# Power_PMIC.net
KiCad netlist of a schematic drawn in Altium Designer
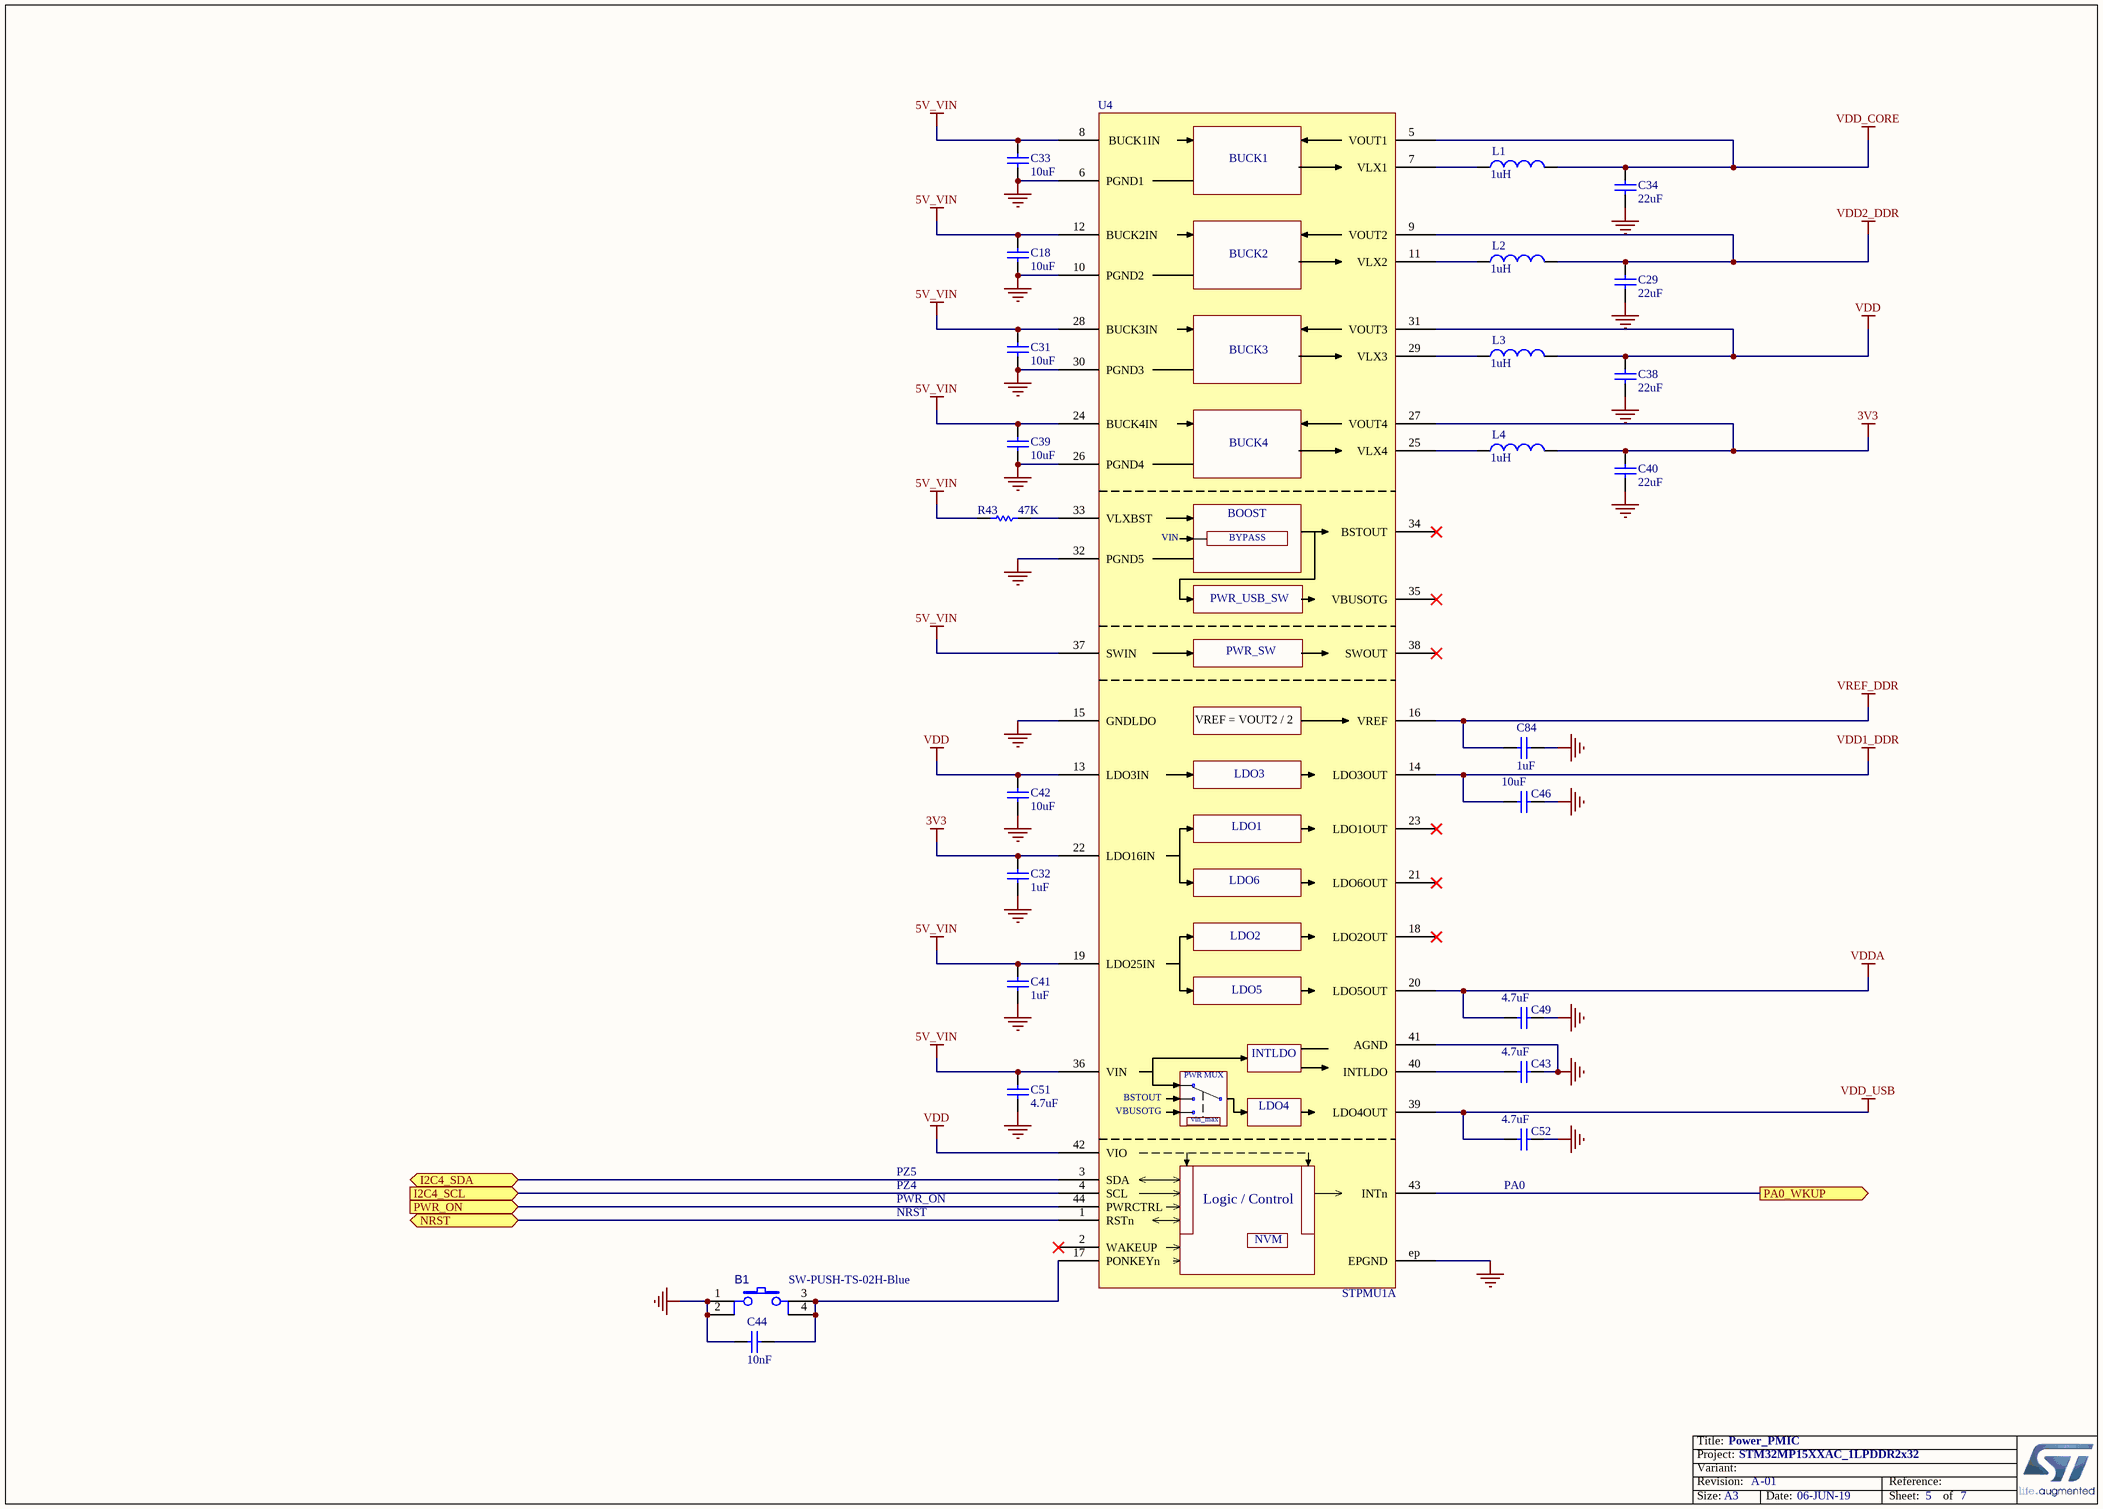
[diagram p0: Power_PMIC.SchDoc]

(export (version "E")
  (design (tool "Eeschema 10.0.6"))
  (components
    (comp (ref "B1")
      (value "SW-PUSH-TS-02H-Blue")
      (footprint "SWI_JIUBABA_C-TS-02H-2-5-B-V-T_R_BLUE")
      (description "Switch HW SMD blue")
      (fields
        (field (name "INTERNAL_PART_NUMBER") "MCD-00172")
        (field (name "MANUFACTURER_PART_NUMBER") "C-TS-02H-2.5-B-V-T/R BLUE")
        (field (name "PROVIDED_BY") "SUBCO")
      )
      (libsource (lib "MCD_PARTS_database") (part "SW-PUSH-TS-02H-Blue"))
    )
    (comp (ref "C18")
      (value "10uF")
      (footprint "C0603")
      (description "Capacitor, MLCC, 10uF, 10V, X5R, 10%, 0603, T=0,8mm")
      (fields
        (field (name "INTERNAL_PART_NUMBER") "MCD-00099")
        (field (name "MANUFACTURER_PART_NUMBER") "GRM188R61A106KE69D")
        (field (name "PROVIDED_BY") "SUBCO")
      )
      (libsource (lib "MCD_PARTS_database") (part "Capacitor"))
    )
    (comp (ref "C29")
      (value "22uF")
      (footprint "C0603")
      (description "Capacitor, MLCC, 22uF, 6V3, X5R, 20%, 0603, T=0,8mm")
      (fields
        (field (name "INTERNAL_PART_NUMBER") "MCD-00100")
        (field (name "MANUFACTURER_PART_NUMBER") "GRM188R60J226MEA0J")
        (field (name "PROVIDED_BY") "SUBCO")
      )
      (libsource (lib "MCD_PARTS_database") (part "Capacitor"))
    )
    (comp (ref "C31")
      (value "10uF")
      (footprint "C0603")
      (description "Capacitor, MLCC, 10uF, 10V, X5R, 10%, 0603, T=0,8mm")
      (fields
        (field (name "INTERNAL_PART_NUMBER") "MCD-00099")
        (field (name "MANUFACTURER_PART_NUMBER") "GRM188R61A106KE69D")
        (field (name "PROVIDED_BY") "SUBCO")
      )
      (libsource (lib "MCD_PARTS_database") (part "Capacitor"))
    )
    (comp (ref "C32")
      (value "1uF")
      (footprint "C0402")
      (description "Capacitor, MLCC, 1uF, 25V, X5R, 10%, 0402, T=0,5mm")
      (fields
        (field (name "INTERNAL_PART_NUMBER") "MCD-00095")
        (field (name "MANUFACTURER_PART_NUMBER") "GRM155R61E105KA12")
        (field (name "PROVIDED_BY") "SUBCO")
      )
      (libsource (lib "MCD_PARTS_database") (part "Capacitor"))
    )
    (comp (ref "C33")
      (value "10uF")
      (footprint "C0603")
      (description "Capacitor, MLCC, 10uF, 10V, X5R, 10%, 0603, T=0,8mm")
      (fields
        (field (name "INTERNAL_PART_NUMBER") "MCD-00099")
        (field (name "MANUFACTURER_PART_NUMBER") "GRM188R61A106KE69D")
        (field (name "PROVIDED_BY") "SUBCO")
      )
      (libsource (lib "MCD_PARTS_database") (part "Capacitor"))
    )
    (comp (ref "C34")
      (value "22uF")
      (footprint "C0603")
      (description "Capacitor, MLCC, 22uF, 6V3, X5R, 20%, 0603, T=0,8mm")
      (fields
        (field (name "INTERNAL_PART_NUMBER") "MCD-00100")
        (field (name "MANUFACTURER_PART_NUMBER") "GRM188R60J226MEA0J")
        (field (name "PROVIDED_BY") "SUBCO")
      )
      (libsource (lib "MCD_PARTS_database") (part "Capacitor"))
    )
    (comp (ref "C38")
      (value "22uF")
      (footprint "C0603")
      (description "Capacitor, MLCC, 22uF, 6V3, X5R, 20%, 0603, T=0,8mm")
      (fields
        (field (name "INTERNAL_PART_NUMBER") "MCD-00100")
        (field (name "MANUFACTURER_PART_NUMBER") "GRM188R60J226MEA0J")
        (field (name "PROVIDED_BY") "SUBCO")
      )
      (libsource (lib "MCD_PARTS_database") (part "Capacitor"))
    )
    (comp (ref "C39")
      (value "10uF")
      (footprint "C0603")
      (description "Capacitor, MLCC, 10uF, 10V, X5R, 10%, 0603, T=0,8mm")
      (fields
        (field (name "INTERNAL_PART_NUMBER") "MCD-00099")
        (field (name "MANUFACTURER_PART_NUMBER") "GRM188R61A106KE69D")
        (field (name "PROVIDED_BY") "SUBCO")
      )
      (libsource (lib "MCD_PARTS_database") (part "Capacitor"))
    )
    (comp (ref "C40")
      (value "22uF")
      (footprint "C0603")
      (description "Capacitor, MLCC, 22uF, 6V3, X5R, 20%, 0603, T=0,8mm")
      (fields
        (field (name "INTERNAL_PART_NUMBER") "MCD-00100")
        (field (name "MANUFACTURER_PART_NUMBER") "GRM188R60J226MEA0J")
        (field (name "PROVIDED_BY") "SUBCO")
      )
      (libsource (lib "MCD_PARTS_database") (part "Capacitor"))
    )
    (comp (ref "C41")
      (value "1uF")
      (footprint "C0402")
      (description "Capacitor, MLCC, 1uF, 25V, X5R, 10%, 0402, T=0,5mm")
      (fields
        (field (name "INTERNAL_PART_NUMBER") "MCD-00095")
        (field (name "MANUFACTURER_PART_NUMBER") "GRM155R61E105KA12")
        (field (name "PROVIDED_BY") "SUBCO")
      )
      (libsource (lib "MCD_PARTS_database") (part "Capacitor"))
    )
    (comp (ref "C42")
      (value "10uF")
      (footprint "C0603")
      (description "Capacitor, MLCC, 10uF, 10V, X5R, 10%, 0603, T=0,8mm")
      (fields
        (field (name "INTERNAL_PART_NUMBER") "MCD-00099")
        (field (name "MANUFACTURER_PART_NUMBER") "GRM188R61A106KE69D")
        (field (name "PROVIDED_BY") "SUBCO")
      )
      (libsource (lib "MCD_PARTS_database") (part "Capacitor"))
    )
    (comp (ref "C43")
      (value "4.7uF")
      (footprint "C0402")
      (description "Capacitor, MLCC, 4.7uF, 6V3, X5R, 20%, 0402, T=0,5mm")
      (fields
        (field (name "INTERNAL_PART_NUMBER") "MCD-00096")
        (field (name "MANUFACTURER_PART_NUMBER") "GRM155R60J475ME87")
        (field (name "PROVIDED_BY") "SUBCO")
      )
      (libsource (lib "MCD_PARTS_database") (part "Capacitor"))
    )
    (comp (ref "C44")
      (value "10nF")
      (footprint "C0402")
      (description "Capacitor, MLCC, 10nF, 16V, X7R, 10%, 0402, T=0.5mm")
      (fields
        (field (name "INTERNAL_PART_NUMBER") "MCD-00011")
        (field (name "MANUFACTURER_PART_NUMBER") "CC0402KRX7R7BB103")
        (field (name "PROVIDED_BY") "SUBCO")
      )
      (libsource (lib "MCD_PARTS_database") (part "Capacitor"))
    )
    (comp (ref "C46")
      (value "10uF")
      (footprint "C0603")
      (description "Capacitor, MLCC, 10uF, 10V, X5R, 10%, 0603, T=0,8mm")
      (fields
        (field (name "INTERNAL_PART_NUMBER") "MCD-00099")
        (field (name "MANUFACTURER_PART_NUMBER") "GRM188R61A106KE69D")
        (field (name "PROVIDED_BY") "SUBCO")
      )
      (libsource (lib "MCD_PARTS_database") (part "Capacitor"))
    )
    (comp (ref "C49")
      (value "4.7uF")
      (footprint "C0402")
      (description "Capacitor, MLCC, 4.7uF, 6V3, X5R, 20%, 0402, T=0,5mm")
      (fields
        (field (name "INTERNAL_PART_NUMBER") "MCD-00096")
        (field (name "MANUFACTURER_PART_NUMBER") "GRM155R60J475ME87")
        (field (name "PROVIDED_BY") "SUBCO")
      )
      (libsource (lib "MCD_PARTS_database") (part "Capacitor"))
    )
    (comp (ref "C51")
      (value "4.7uF")
      (footprint "C0402")
      (description "Capacitor, MLCC, 4.7uF, 6V3, X5R, 20%, 0402, T=0,5mm")
      (fields
        (field (name "INTERNAL_PART_NUMBER") "MCD-00096")
        (field (name "MANUFACTURER_PART_NUMBER") "GRM155R60J475ME87")
        (field (name "PROVIDED_BY") "SUBCO")
      )
      (libsource (lib "MCD_PARTS_database") (part "Capacitor"))
    )
    (comp (ref "C52")
      (value "4.7uF")
      (footprint "C0402")
      (description "Capacitor, MLCC, 4.7uF, 6V3, X5R, 20%, 0402, T=0,5mm")
      (fields
        (field (name "INTERNAL_PART_NUMBER") "MCD-00096")
        (field (name "MANUFACTURER_PART_NUMBER") "GRM155R60J475ME87")
        (field (name "PROVIDED_BY") "SUBCO")
      )
      (libsource (lib "MCD_PARTS_database") (part "Capacitor"))
    )
    (comp (ref "C84")
      (value "1uF")
      (footprint "C0402")
      (description "Capacitor, MLCC, 1uF, 25V, X5R, 10%, 0402, T=0,5mm")
      (fields
        (field (name "INTERNAL_PART_NUMBER") "MCD-00095")
        (field (name "MANUFACTURER_PART_NUMBER") "GRM155R61E105KA12")
        (field (name "PROVIDED_BY") "SUBCO")
      )
      (libsource (lib "MCD_PARTS_database") (part "Capacitor"))
    )
    (comp (ref "L1")
      (value "1uH")
      (footprint "IND_2520_TOKO_DFE252012P")
      (description "Power Inductor ,1uH,4.3A max,+/-20%,0.042ohm,2520")
      (fields
        (field (name "INTERNAL_PART_NUMBER") "MCD-01122")
        (field (name "MANUFACTURER_PART_NUMBER") "DFE252012P-1ROM=P2")
        (field (name "PROVIDED_BY") "SUBCO")
      )
      (libsource (lib "MCD_PARTS_database") (part "IND_1uH_42mohm_3.2A"))
    )
    (comp (ref "L2")
      (value "1uH")
      (footprint "IND_2520_TOKO_DFE252012P")
      (description "Power Inductor ,1uH,4.3A max,+/-20%,0.042ohm,2520")
      (fields
        (field (name "INTERNAL_PART_NUMBER") "MCD-01122")
        (field (name "MANUFACTURER_PART_NUMBER") "DFE252012P-1ROM=P2")
        (field (name "PROVIDED_BY") "SUBCO")
      )
      (libsource (lib "MCD_PARTS_database") (part "IND_1uH_42mohm_3.2A"))
    )
    (comp (ref "L3")
      (value "1uH")
      (footprint "IND_2520_TOKO_DFE252012P")
      (description "Power Inductor ,1uH,4.3A max,+/-20%,0.042ohm,2520")
      (fields
        (field (name "INTERNAL_PART_NUMBER") "MCD-01122")
        (field (name "MANUFACTURER_PART_NUMBER") "DFE252012P-1ROM=P2")
        (field (name "PROVIDED_BY") "SUBCO")
      )
      (libsource (lib "MCD_PARTS_database") (part "IND_1uH_42mohm_3.2A"))
    )
    (comp (ref "L4")
      (value "1uH")
      (footprint "IND_2520_TOKO_DFE252012P")
      (description "Power Inductor ,1uH,4.3A max,+/-20%,0.042ohm,2520")
      (fields
        (field (name "INTERNAL_PART_NUMBER") "MCD-01122")
        (field (name "MANUFACTURER_PART_NUMBER") "DFE252012P-1ROM=P2")
        (field (name "PROVIDED_BY") "SUBCO")
      )
      (libsource (lib "MCD_PARTS_database") (part "IND_1uH_42mohm_3.2A"))
    )
    (comp (ref "R43")
      (value "47K")
      (footprint "R0402")
      (description "Resistor,47K,0402,1%,1/16W")
      (fields
        (field (name "INTERNAL_PART_NUMBER") "MCD-00063")
        (field (name "MANUFACTURER_PART_NUMBER") "RC0402FR-0747KL")
        (field (name "PROVIDED_BY") "SUBCO")
      )
      (libsource (lib "MCD_PARTS_database") (part "Resistor"))
    )
    (comp (ref "U4")
      (value "STPMU1A")
      (footprint "ICC_WFQFN44-EPAD_5X6_P040")
      (description "STM PMIC WFQFN 5.0x6.0x0.80 44L 0.4 pitch")
      (fields
        (field (name "INTERNAL_PART_NUMBER") "MCD-00303")
        (field (name "MANUFACTURER_PART_NUMBER") "STPMU1APQR")
        (field (name "PROVIDED_BY") "SUBCO with ST control")
      )
      (libsource (lib "MCD_PARTS_database") (part "STPMU1"))
    )
  )
  (nets
    (net (code "1") (name "/I2C4_SCL") (class "Default")
      (node (ref "U4") (pin "4") (pinfunction "SCL_4") (pintype "passive"))
    )
    (net (code "2") (name "/I2C4_SDA") (class "Default")
      (node (ref "U4") (pin "3") (pinfunction "SDA_3") (pintype "passive"))
    )
    (net (code "3") (name "/NRST") (class "Default")
      (node (ref "U4") (pin "1") (pinfunction "RSTn_1") (pintype "passive"))
    )
    (net (code "4") (name "/PA0_WKUP") (class "Default")
      (node (ref "U4") (pin "43") (pinfunction "INTn_43") (pintype "passive"))
    )
    (net (code "5") (name "/PWR_ON") (class "Default")
      (node (ref "U4") (pin "44") (pinfunction "PWRCTRL_44") (pintype "passive"))
    )
    (net (code "6") (name "3V3") (class "Default")
      (node (ref "C32") (pin "2") (pinfunction "2_2") (pintype "passive"))
      (node (ref "C40") (pin "2") (pinfunction "2_2") (pintype "passive"))
      (node (ref "L4") (pin "2") (pinfunction "2_2") (pintype "passive"))
      (node (ref "U4") (pin "22") (pinfunction "LDO16IN_22") (pintype "passive"))
      (node (ref "U4") (pin "27") (pinfunction "VOUT4_27") (pintype "passive"))
    )
    (net (code "7") (name "5V_VIN") (class "Default")
      (node (ref "C18") (pin "2") (pinfunction "2_2") (pintype "passive"))
      (node (ref "C31") (pin "2") (pinfunction "2_2") (pintype "passive"))
      (node (ref "C33") (pin "2") (pinfunction "2_2") (pintype "passive"))
      (node (ref "C39") (pin "2") (pinfunction "2_2") (pintype "passive"))
      (node (ref "C41") (pin "2") (pinfunction "2_2") (pintype "passive"))
      (node (ref "C51") (pin "2") (pinfunction "2_2") (pintype "passive"))
      (node (ref "R43") (pin "2") (pinfunction "2_2") (pintype "passive"))
      (node (ref "U4") (pin "12") (pinfunction "BUCK2IN_12") (pintype "passive"))
      (node (ref "U4") (pin "19") (pinfunction "LDO25IN_19") (pintype "passive"))
      (node (ref "U4") (pin "24") (pinfunction "BUCK4IN_24") (pintype "passive"))
      (node (ref "U4") (pin "28") (pinfunction "BUCK3IN_28") (pintype "passive"))
      (node (ref "U4") (pin "36") (pinfunction "VIN_36") (pintype "passive"))
      (node (ref "U4") (pin "37") (pinfunction "SWIN_37") (pintype "passive"))
      (node (ref "U4") (pin "8") (pinfunction "BUCK1IN_8") (pintype "passive"))
    )
    (net (code "8") (name "GND") (class "Default")
      (node (ref "B1") (pin "1") (pinfunction "1_1") (pintype "passive"))
      (node (ref "B1") (pin "2") (pinfunction "2_2") (pintype "passive"))
      (node (ref "C18") (pin "1") (pinfunction "1_1") (pintype "passive"))
      (node (ref "C29") (pin "1") (pinfunction "1_1") (pintype "passive"))
      (node (ref "C31") (pin "1") (pinfunction "1_1") (pintype "passive"))
      (node (ref "C32") (pin "1") (pinfunction "1_1") (pintype "passive"))
      (node (ref "C33") (pin "1") (pinfunction "1_1") (pintype "passive"))
      (node (ref "C34") (pin "1") (pinfunction "1_1") (pintype "passive"))
      (node (ref "C38") (pin "1") (pinfunction "1_1") (pintype "passive"))
      (node (ref "C39") (pin "1") (pinfunction "1_1") (pintype "passive"))
      (node (ref "C40") (pin "1") (pinfunction "1_1") (pintype "passive"))
      (node (ref "C41") (pin "1") (pinfunction "1_1") (pintype "passive"))
      (node (ref "C42") (pin "1") (pinfunction "1_1") (pintype "passive"))
      (node (ref "C43") (pin "2") (pinfunction "2_2") (pintype "passive"))
      (node (ref "C44") (pin "1") (pinfunction "1_1") (pintype "passive"))
      (node (ref "C46") (pin "1") (pinfunction "1_1") (pintype "passive"))
      (node (ref "C49") (pin "1") (pinfunction "1_1") (pintype "passive"))
      (node (ref "C51") (pin "1") (pinfunction "1_1") (pintype "passive"))
      (node (ref "C52") (pin "1") (pinfunction "1_1") (pintype "passive"))
      (node (ref "C84") (pin "1") (pinfunction "1_1") (pintype "passive"))
      (node (ref "U4") (pin "10") (pinfunction "PGND2_10") (pintype "passive"))
      (node (ref "U4") (pin "15") (pinfunction "GNDLDO_15") (pintype "passive"))
      (node (ref "U4") (pin "26") (pinfunction "PGND4_26") (pintype "passive"))
      (node (ref "U4") (pin "30") (pinfunction "PGND3_30") (pintype "passive"))
      (node (ref "U4") (pin "32") (pinfunction "PGND5_32") (pintype "passive"))
      (node (ref "U4") (pin "41") (pinfunction "AGND_41") (pintype "passive"))
      (node (ref "U4") (pin "6") (pinfunction "PGND1_6") (pintype "passive"))
      (node (ref "U4") (pin "ep") (pinfunction "EPGND_ep") (pintype "passive"))
    )
    (net (code "9") (name "Net-(U4-INTLDO)") (class "Default")
      (node (ref "C43") (pin "1") (pinfunction "1_1") (pintype "passive"))
      (node (ref "U4") (pin "40") (pinfunction "INTLDO_40") (pintype "passive"))
    )
    (net (code "10") (name "Net-(U4-PONKEYn)") (class "Default")
      (node (ref "B1") (pin "3") (pinfunction "3_3") (pintype "passive"))
      (node (ref "B1") (pin "4") (pinfunction "4_4") (pintype "passive"))
      (node (ref "C44") (pin "2") (pinfunction "2_2") (pintype "passive"))
      (node (ref "U4") (pin "17") (pinfunction "PONKEYn_17") (pintype "passive"))
    )
    (net (code "11") (name "Net-(U4-VLX1)") (class "Default")
      (node (ref "L1") (pin "1") (pinfunction "1_1") (pintype "passive"))
      (node (ref "U4") (pin "7") (pinfunction "VLX1_7") (pintype "passive"))
    )
    (net (code "12") (name "Net-(U4-VLX2)") (class "Default")
      (node (ref "L2") (pin "1") (pinfunction "1_1") (pintype "passive"))
      (node (ref "U4") (pin "11") (pinfunction "VLX2_11") (pintype "passive"))
    )
    (net (code "13") (name "Net-(U4-VLX3)") (class "Default")
      (node (ref "L3") (pin "1") (pinfunction "1_1") (pintype "passive"))
      (node (ref "U4") (pin "29") (pinfunction "VLX3_29") (pintype "passive"))
    )
    (net (code "14") (name "Net-(U4-VLX4)") (class "Default")
      (node (ref "L4") (pin "1") (pinfunction "1_1") (pintype "passive"))
      (node (ref "U4") (pin "25") (pinfunction "VLX4_25") (pintype "passive"))
    )
    (net (code "15") (name "Net-(U4-VLXBST)") (class "Default")
      (node (ref "R43") (pin "1") (pinfunction "1_1") (pintype "passive"))
      (node (ref "U4") (pin "33") (pinfunction "VLXBST_33") (pintype "passive"))
    )
    (net (code "16") (name "VDD") (class "Default")
      (node (ref "C38") (pin "2") (pinfunction "2_2") (pintype "passive"))
      (node (ref "C42") (pin "2") (pinfunction "2_2") (pintype "passive"))
      (node (ref "L3") (pin "2") (pinfunction "2_2") (pintype "passive"))
      (node (ref "U4") (pin "13") (pinfunction "LDO3IN_13") (pintype "passive"))
      (node (ref "U4") (pin "31") (pinfunction "VOUT3_31") (pintype "passive"))
      (node (ref "U4") (pin "42") (pinfunction "VIO_42") (pintype "passive"))
    )
    (net (code "17") (name "VDD1_DDR") (class "Default")
      (node (ref "C46") (pin "2") (pinfunction "2_2") (pintype "passive"))
      (node (ref "U4") (pin "14") (pinfunction "LDO3OUT_14") (pintype "passive"))
    )
    (net (code "18") (name "VDD2_DDR") (class "Default")
      (node (ref "C29") (pin "2") (pinfunction "2_2") (pintype "passive"))
      (node (ref "L2") (pin "2") (pinfunction "2_2") (pintype "passive"))
      (node (ref "U4") (pin "9") (pinfunction "VOUT2_9") (pintype "passive"))
    )
    (net (code "19") (name "VDDA") (class "Default")
      (node (ref "C49") (pin "2") (pinfunction "2_2") (pintype "passive"))
      (node (ref "U4") (pin "20") (pinfunction "LDO5OUT_20") (pintype "passive"))
    )
    (net (code "20") (name "VDD_CORE") (class "Default")
      (node (ref "C34") (pin "2") (pinfunction "2_2") (pintype "passive"))
      (node (ref "L1") (pin "2") (pinfunction "2_2") (pintype "passive"))
      (node (ref "U4") (pin "5") (pinfunction "VOUT1_5") (pintype "passive"))
    )
    (net (code "21") (name "VDD_USB") (class "Default")
      (node (ref "C52") (pin "2") (pinfunction "2_2") (pintype "passive"))
      (node (ref "U4") (pin "39") (pinfunction "LDO4OUT_39") (pintype "passive"))
    )
    (net (code "22") (name "VREF_DDR") (class "Default")
      (node (ref "C84") (pin "2") (pinfunction "2_2") (pintype "passive"))
      (node (ref "U4") (pin "16") (pinfunction "VREF_16") (pintype "passive"))
    )
    (net (code "23") (name "unconnected-(U4-BSTOUT-Pad34)") (class "Default")
      (node (ref "U4") (pin "34") (pinfunction "BSTOUT_34") (pintype "passive+no_connect"))
    )
    (net (code "24") (name "unconnected-(U4-LDO1OUT-Pad23)") (class "Default")
      (node (ref "U4") (pin "23") (pinfunction "LDO1OUT_23") (pintype "passive+no_connect"))
    )
    (net (code "25") (name "unconnected-(U4-LDO2OUT-Pad18)") (class "Default")
      (node (ref "U4") (pin "18") (pinfunction "LDO2OUT_18") (pintype "passive+no_connect"))
    )
    (net (code "26") (name "unconnected-(U4-LDO6OUT-Pad21)") (class "Default")
      (node (ref "U4") (pin "21") (pinfunction "LDO6OUT_21") (pintype "passive+no_connect"))
    )
    (net (code "27") (name "unconnected-(U4-SWOUT-Pad38)") (class "Default")
      (node (ref "U4") (pin "38") (pinfunction "SWOUT_38") (pintype "passive+no_connect"))
    )
    (net (code "28") (name "unconnected-(U4-VBUSOTG-Pad35)") (class "Default")
      (node (ref "U4") (pin "35") (pinfunction "VBUSOTG_35") (pintype "passive+no_connect"))
    )
    (net (code "29") (name "unconnected-(U4-WAKEUP-Pad2)") (class "Default")
      (node (ref "U4") (pin "2") (pinfunction "WAKEUP_2") (pintype "passive+no_connect"))
    )
  )
)
